# IoT_Remote_Control.net
KiCad netlist of a schematic drawn in EAGLE
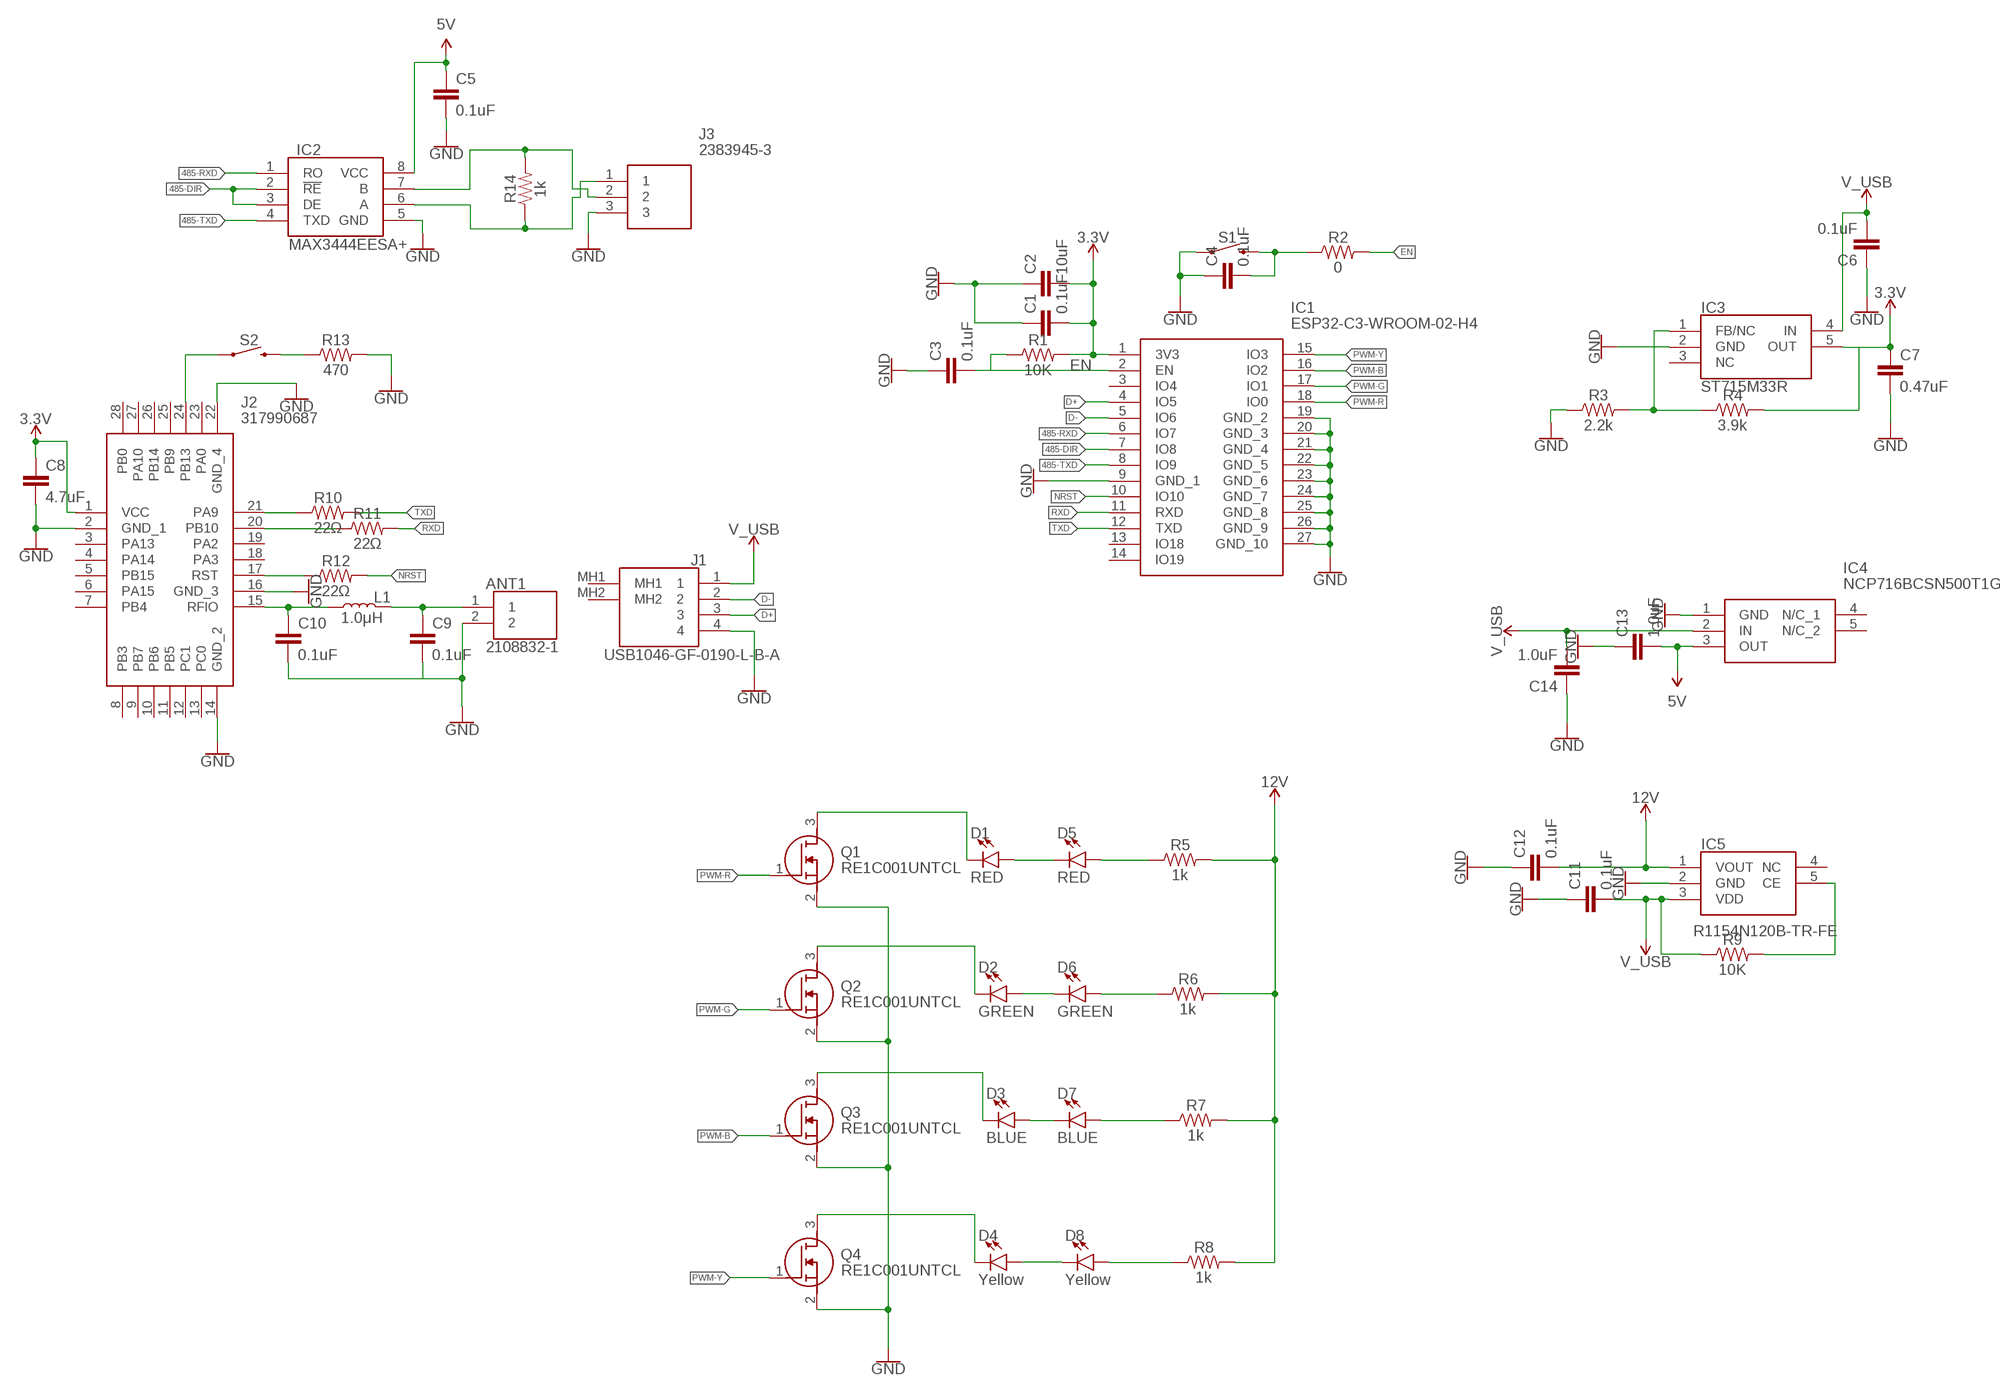
[diagram p0: schematic, sheet 1]

(export (version "E")
  (design (tool "Eeschema 10.0.6"))
  (components
    (comp (ref "ANT1")
      (value "2108832-1")
      (footprint "eagle-import:21088321")
      (libsource (lib "eagle-import") (part "2108832-1"))
    )
    (comp (ref "C1")
      (value "0.1uF")
      (footprint "eagle-import:0402-TIGHT")
      (libsource (lib "eagle-import") (part "0.1UF-0402T-6.3V-10%-X7R"))
    )
    (comp (ref "C2")
      (value "10uF")
      (footprint "eagle-import:0402-TIGHT")
      (libsource (lib "eagle-import") (part "10UF-0402T-6.3V-20%"))
    )
    (comp (ref "C3")
      (value "0.1uF")
      (footprint "eagle-import:0402-TIGHT")
      (libsource (lib "eagle-import") (part "0.1UF-0402T-6.3V-10%-X7R"))
    )
    (comp (ref "C4")
      (value "0.1uF")
      (footprint "eagle-import:0402-TIGHT")
      (libsource (lib "eagle-import") (part "0.1UF-0402T-6.3V-10%-X7R"))
    )
    (comp (ref "C5")
      (value "0.1uF")
      (footprint "eagle-import:0402-TIGHT")
      (libsource (lib "eagle-import") (part "0.1UF-0402T-6.3V-10%-X7R"))
    )
    (comp (ref "C6")
      (value "0.1uF")
      (footprint "eagle-import:0402-TIGHT")
      (libsource (lib "eagle-import") (part "0.1UF-0402T-6.3V-10%-X7R"))
    )
    (comp (ref "C7")
      (value "0.47uF")
      (footprint "eagle-import:0402-TIGHT")
      (libsource (lib "eagle-import") (part "470NF-0402_TIGHT-6.3V-10%-X5R"))
    )
    (comp (ref "C8")
      (value "4.7uF")
      (footprint "eagle-import:0402-TIGHT")
      (libsource (lib "eagle-import") (part "4.7UF-0402_TIGHT-6.3V-20%-X5R"))
    )
    (comp (ref "C9")
      (value "0.1uF")
      (footprint "eagle-import:0402-TIGHT")
      (libsource (lib "eagle-import") (part "0.1UF-0402T-6.3V-10%-X7R"))
    )
    (comp (ref "C10")
      (value "0.1uF")
      (footprint "eagle-import:0402-TIGHT")
      (libsource (lib "eagle-import") (part "0.1UF-0402T-6.3V-10%-X7R"))
    )
    (comp (ref "C11")
      (value "0.1uF")
      (footprint "eagle-import:0402-TIGHT")
      (libsource (lib "eagle-import") (part "0.1UF-0402T-6.3V-10%-X7R"))
    )
    (comp (ref "C12")
      (value "0.1uF")
      (footprint "eagle-import:0402-TIGHT")
      (libsource (lib "eagle-import") (part "0.1UF-0402T-6.3V-10%-X7R"))
    )
    (comp (ref "C13")
      (value "1.0uF")
      (footprint "eagle-import:0402-TIGHT")
      (libsource (lib "eagle-import") (part "1.0UF-0402T-16V-10%"))
    )
    (comp (ref "C14")
      (value "1.0uF")
      (footprint "eagle-import:0402-TIGHT")
      (libsource (lib "eagle-import") (part "1.0UF-0402T-16V-10%"))
    )
    (comp (ref "D1")
      (value "RED")
      (footprint "eagle-import:LED-0603")
      (libsource (lib "eagle-import") (part "LED-RED0603"))
    )
    (comp (ref "D2")
      (value "GREEN")
      (footprint "eagle-import:LED-0603")
      (libsource (lib "eagle-import") (part "LED-GREEN0603"))
    )
    (comp (ref "D3")
      (value "BLUE")
      (footprint "eagle-import:LED-0603")
      (libsource (lib "eagle-import") (part "LED-BLUE0603"))
    )
    (comp (ref "D4")
      (value "Yellow")
      (footprint "eagle-import:LED-0603")
      (libsource (lib "eagle-import") (part "LED-YELLOW0603"))
    )
    (comp (ref "D5")
      (value "RED")
      (footprint "eagle-import:LED-0603")
      (libsource (lib "eagle-import") (part "LED-RED0603"))
    )
    (comp (ref "D6")
      (value "GREEN")
      (footprint "eagle-import:LED-0603")
      (libsource (lib "eagle-import") (part "LED-GREEN0603"))
    )
    (comp (ref "D7")
      (value "BLUE")
      (footprint "eagle-import:LED-0603")
      (libsource (lib "eagle-import") (part "LED-BLUE0603"))
    )
    (comp (ref "D8")
      (value "Yellow")
      (footprint "eagle-import:LED-0603")
      (libsource (lib "eagle-import") (part "LED-YELLOW0603"))
    )
    (comp (ref "IC1")
      (value "ESP32-C3-WROOM-02-H4")
      (footprint "eagle-import:ESP32C3WROOM02H4")
      (fields (field (name "MOUSER_PART_NUMBER") "356-ESP32C3WROOM02H4"))
      (libsource (lib "eagle-import") (part "ESP32-C3-WROOM-02-H4"))
    )
    (comp (ref "IC2")
      (value "MAX3444EESA+")
      (footprint "eagle-import:SOIC127P600X175-8N")
      (fields (field (name "MOUSER_PART_NUMBER") "700-MAX3444EESA"))
      (libsource (lib "eagle-import") (part "MAX3444EESA+"))
    )
    (comp (ref "IC3")
      (value "ST715M33R")
      (footprint "eagle-import:SOT95P280X145-5N")
      (fields (field (name "MOUSER_PART_NUMBER") "511-ST715M33R"))
      (libsource (lib "eagle-import") (part "ST715M33R"))
    )
    (comp (ref "IC4")
      (value "NCP716BCSN500T1G")
      (footprint "eagle-import:SOT95P275X110-5N")
      (fields (field (name "MOUSER_PART_NUMBER") "863-NCP716BCSN500T1G"))
      (libsource (lib "eagle-import") (part "NCP716BCSN500T1G"))
    )
    (comp (ref "IC5")
      (value "R1154N120B-TR-FE")
      (footprint "eagle-import:SOT95P280X130-5N")
      (libsource (lib "eagle-import") (part "R1154N120B-TR-FE"))
    )
    (comp (ref "J1")
      (value "USB1046-GF-0190-L-B-A")
      (footprint "eagle-import:USB1046GF0190LBA")
      (fields (field (name "MOUSER_PART_NUMBER") "640-USB1046GF0190LBA"))
      (libsource (lib "eagle-import") (part "USB1046-GF-0190-L-B-A"))
    )
    (comp (ref "J2")
      (value "317990687")
      (footprint "eagle-import:317990687")
      (fields (field (name "MOUSER_PART_NUMBER") "713-317990687"))
      (libsource (lib "eagle-import") (part "317990687"))
    )
    (comp (ref "J3")
      (value "2383945-3")
      (footprint "eagle-import:23839453")
      (fields (field (name "MOUSER_PART_NUMBER") "571-2383945-3"))
      (libsource (lib "eagle-import") (part "2383945-3"))
    )
    (comp (ref "L1")
      (value "1.0μH")
      (footprint "eagle-import:0805-WIDE")
      (libsource (lib "eagle-import") (part "1.0μH-0805_WIDE-1.0μH-1.4A-0.07OHM-1.4MM_H"))
    )
    (comp (ref "Q1")
      (value "RE1C001UNTCL")
      (footprint "eagle-import:SOTFL50P160X85-3N")
      (fields (field (name "MOUSER_PART_NUMBER") "755-RE1C001UNTCL"))
      (libsource (lib "eagle-import") (part "RE1C001UNTCL"))
    )
    (comp (ref "Q2")
      (value "RE1C001UNTCL")
      (footprint "eagle-import:SOTFL50P160X85-3N")
      (fields (field (name "MOUSER_PART_NUMBER") "755-RE1C001UNTCL"))
      (libsource (lib "eagle-import") (part "RE1C001UNTCL"))
    )
    (comp (ref "Q3")
      (value "RE1C001UNTCL")
      (footprint "eagle-import:SOTFL50P160X85-3N")
      (fields (field (name "MOUSER_PART_NUMBER") "755-RE1C001UNTCL"))
      (libsource (lib "eagle-import") (part "RE1C001UNTCL"))
    )
    (comp (ref "Q4")
      (value "RE1C001UNTCL")
      (footprint "eagle-import:SOTFL50P160X85-3N")
      (fields (field (name "MOUSER_PART_NUMBER") "755-RE1C001UNTCL"))
      (libsource (lib "eagle-import") (part "RE1C001UNTCL"))
    )
    (comp (ref "R1")
      (value "10K")
      (footprint "eagle-import:0402-TIGHT")
      (libsource (lib "eagle-import") (part "10KOHM-0402-1/10W-0.1%"))
    )
    (comp (ref "R2")
      (value "0")
      (footprint "eagle-import:0402-TIGHT")
      (libsource (lib "eagle-import") (part "0OHM-0402T-1/10W"))
    )
    (comp (ref "R3")
      (value "2.2k")
      (footprint "eagle-import:0402-TIGHT")
      (libsource (lib "eagle-import") (part "2.2KOHM-0402T-1/16W-1%"))
    )
    (comp (ref "R4")
      (value "3.9k")
      (footprint "eagle-import:0603")
      (libsource (lib "eagle-import") (part "3.9KOHM-0603-1/10W-1%"))
    )
    (comp (ref "R5")
      (value "1k")
      (footprint "eagle-import:0402-TIGHT")
      (libsource (lib "eagle-import") (part "1KOHM-0402T-1/16W-1%"))
    )
    (comp (ref "R6")
      (value "1k")
      (footprint "eagle-import:0402-TIGHT")
      (libsource (lib "eagle-import") (part "1KOHM-0402T-1/16W-1%"))
    )
    (comp (ref "R7")
      (value "1k")
      (footprint "eagle-import:0402-TIGHT")
      (libsource (lib "eagle-import") (part "1KOHM-0402T-1/16W-1%"))
    )
    (comp (ref "R8")
      (value "1k")
      (footprint "eagle-import:0402-TIGHT")
      (libsource (lib "eagle-import") (part "1KOHM-0402T-1/16W-1%"))
    )
    (comp (ref "R9")
      (value "10K")
      (footprint "eagle-import:0402-TIGHT")
      (libsource (lib "eagle-import") (part "10KOHM-0402-1/10W-0.1%"))
    )
    (comp (ref "R10")
      (value "22Ω")
      (footprint "eagle-import:0402-TIGHT")
      (libsource (lib "eagle-import") (part "22OHM-0402T-1/16W-1%"))
    )
    (comp (ref "R11")
      (value "22Ω")
      (footprint "eagle-import:0402-TIGHT")
      (libsource (lib "eagle-import") (part "22OHM-0402T-1/16W-1%"))
    )
    (comp (ref "R12")
      (value "22Ω")
      (footprint "eagle-import:0402-TIGHT")
      (libsource (lib "eagle-import") (part "22OHM-0402T-1/16W-1%"))
    )
    (comp (ref "R13")
      (value "470")
      (footprint "eagle-import:0402-TIGHT")
      (libsource (lib "eagle-import") (part "470OHM-0402-TIGHT-1/16W-1%"))
    )
    (comp (ref "R14")
      (value "1k")
      (footprint "eagle-import:0402-TIGHT")
      (libsource (lib "eagle-import") (part "1KOHM-0402T-1/16W-1%"))
    )
    (comp (ref "S1")
      (value "MOMENTARY-SWITCH-SPST-SMD-4.6X2.8MM")
      (footprint "eagle-import:TACTILE_SWITCH_SMD_4.6X2.8MM")
      (libsource (lib "eagle-import") (part "MOMENTARY-SWITCH-SPST-SMD-4.6X2.8MM"))
    )
    (comp (ref "S2")
      (value "MOMENTARY-SWITCH-SPST-SMD-4.6X2.8MM")
      (footprint "eagle-import:TACTILE_SWITCH_SMD_4.6X2.8MM")
      (libsource (lib "eagle-import") (part "MOMENTARY-SWITCH-SPST-SMD-4.6X2.8MM"))
    )
  )
  (nets
    (net (code "1") (name "3.3V") (class "Default")
      (node (ref "C1") (pin "2") (pinfunction "2_2") (pintype "passive"))
      (node (ref "C2") (pin "2") (pinfunction "2_2") (pintype "passive"))
      (node (ref "C7") (pin "1") (pinfunction "1_1") (pintype "passive"))
      (node (ref "C8") (pin "1") (pinfunction "1_1") (pintype "passive"))
      (node (ref "IC1") (pin "1") (pinfunction "3V3_1") (pintype "bidirectional"))
      (node (ref "IC3") (pin "5") (pinfunction "OUT_5") (pintype "output"))
      (node (ref "J2") (pin "1") (pinfunction "VCC_1") (pintype "bidirectional"))
      (node (ref "R1") (pin "2") (pinfunction "2_2") (pintype "passive"))
      (node (ref "R4") (pin "2") (pinfunction "2_2") (pintype "passive"))
    )
    (net (code "2") (name "5V") (class "Default")
      (node (ref "C13") (pin "2") (pinfunction "2_2") (pintype "passive"))
      (node (ref "C5") (pin "1") (pinfunction "1_1") (pintype "passive"))
      (node (ref "IC2") (pin "8") (pinfunction "VCC_8") (pintype "bidirectional"))
      (node (ref "IC4") (pin "3") (pinfunction "OUT_3") (pintype "bidirectional"))
    )
    (net (code "3") (name "12V") (class "Default")
      (node (ref "C12") (pin "2") (pinfunction "2_2") (pintype "passive"))
      (node (ref "IC5") (pin "1") (pinfunction "VOUT_1") (pintype "bidirectional"))
      (node (ref "R5") (pin "2") (pinfunction "2_2") (pintype "passive"))
      (node (ref "R6") (pin "2") (pinfunction "2_2") (pintype "passive"))
      (node (ref "R7") (pin "2") (pinfunction "2_2") (pintype "passive"))
      (node (ref "R8") (pin "2") (pinfunction "2_2") (pintype "passive"))
    )
    (net (code "4") (name "485-DIR") (class "Default")
      (node (ref "IC1") (pin "7") (pinfunction "IO8_7") (pintype "bidirectional"))
      (node (ref "IC2") (pin "2") (pinfunction "~{RE}_2") (pintype "bidirectional"))
      (node (ref "IC2") (pin "3") (pinfunction "DE_3") (pintype "bidirectional"))
    )
    (net (code "5") (name "485-RXD") (class "Default")
      (node (ref "IC1") (pin "6") (pinfunction "IO7_6") (pintype "bidirectional"))
      (node (ref "IC2") (pin "1") (pinfunction "RO_1") (pintype "bidirectional"))
    )
    (net (code "6") (name "485-TXD") (class "Default")
      (node (ref "IC1") (pin "8") (pinfunction "IO9_8") (pintype "bidirectional"))
      (node (ref "IC2") (pin "4") (pinfunction "TXD_4") (pintype "bidirectional"))
    )
    (net (code "7") (name "D+") (class "Default")
      (node (ref "IC1") (pin "4") (pinfunction "IO5_4") (pintype "bidirectional"))
      (node (ref "J1") (pin "3") (pinfunction "3_3") (pintype "bidirectional"))
    )
    (net (code "8") (name "D-") (class "Default")
      (node (ref "IC1") (pin "5") (pinfunction "IO6_5") (pintype "bidirectional"))
      (node (ref "J1") (pin "2") (pinfunction "2_2") (pintype "bidirectional"))
    )
    (net (code "9") (name "EN") (class "Default")
      (node (ref "C3") (pin "2") (pinfunction "2_2") (pintype "passive"))
      (node (ref "IC1") (pin "2") (pinfunction "EN_2") (pintype "bidirectional"))
      (node (ref "R2") (pin "2") (pinfunction "2_2") (pintype "passive"))
    )
    (net (code "10") (name "GND") (class "Default")
      (node (ref "ANT1") (pin "2") (pinfunction "2_2") (pintype "bidirectional"))
      (node (ref "C1") (pin "1") (pinfunction "1_1") (pintype "passive"))
      (node (ref "C10") (pin "2") (pinfunction "2_2") (pintype "passive"))
      (node (ref "C11") (pin "1") (pinfunction "1_1") (pintype "passive"))
      (node (ref "C12") (pin "1") (pinfunction "1_1") (pintype "passive"))
      (node (ref "C13") (pin "1") (pinfunction "1_1") (pintype "passive"))
      (node (ref "C14") (pin "1") (pinfunction "1_1") (pintype "passive"))
      (node (ref "C2") (pin "1") (pinfunction "1_1") (pintype "passive"))
      (node (ref "C3") (pin "1") (pinfunction "1_1") (pintype "passive"))
      (node (ref "C4") (pin "1") (pinfunction "1_1") (pintype "passive"))
      (node (ref "C5") (pin "2") (pinfunction "2_2") (pintype "passive"))
      (node (ref "C6") (pin "1") (pinfunction "1_1") (pintype "passive"))
      (node (ref "C7") (pin "2") (pinfunction "2_2") (pintype "passive"))
      (node (ref "C8") (pin "2") (pinfunction "2_2") (pintype "passive"))
      (node (ref "IC1") (pin "19") (pinfunction "GND_2_19") (pintype "bidirectional"))
      (node (ref "IC1") (pin "20") (pinfunction "GND_3_20") (pintype "bidirectional"))
      (node (ref "IC1") (pin "21") (pinfunction "GND_4_21") (pintype "bidirectional"))
      (node (ref "IC1") (pin "22") (pinfunction "GND_5_22") (pintype "bidirectional"))
      (node (ref "IC1") (pin "23") (pinfunction "GND_6_23") (pintype "bidirectional"))
      (node (ref "IC1") (pin "24") (pinfunction "GND_7_24") (pintype "bidirectional"))
      (node (ref "IC1") (pin "25") (pinfunction "GND_8_25") (pintype "bidirectional"))
      (node (ref "IC1") (pin "26") (pinfunction "GND_9_26") (pintype "bidirectional"))
      (node (ref "IC1") (pin "27") (pinfunction "GND_10_27") (pintype "bidirectional"))
      (node (ref "IC1") (pin "9") (pinfunction "GND_1_9") (pintype "bidirectional"))
      (node (ref "IC2") (pin "5") (pinfunction "GND_5") (pintype "bidirectional"))
      (node (ref "IC3") (pin "2") (pinfunction "GND_2") (pintype "power_in"))
      (node (ref "IC4") (pin "1") (pinfunction "GND_1") (pintype "bidirectional"))
      (node (ref "IC5") (pin "2") (pinfunction "GND_2") (pintype "bidirectional"))
      (node (ref "J1") (pin "4") (pinfunction "4_4") (pintype "bidirectional"))
      (node (ref "J2") (pin "14") (pinfunction "GND_2_14") (pintype "bidirectional"))
      (node (ref "J2") (pin "16") (pinfunction "GND_3_16") (pintype "bidirectional"))
      (node (ref "J2") (pin "2") (pinfunction "GND_1_2") (pintype "bidirectional"))
      (node (ref "J2") (pin "22") (pinfunction "GND_4_22") (pintype "bidirectional"))
      (node (ref "J3") (pin "3") (pinfunction "3_3") (pintype "bidirectional"))
      (node (ref "Q1") (pin "2") (pinfunction "S_2") (pintype "bidirectional"))
      (node (ref "Q2") (pin "2") (pinfunction "S_2") (pintype "bidirectional"))
      (node (ref "Q3") (pin "2") (pinfunction "S_2") (pintype "bidirectional"))
      (node (ref "Q4") (pin "2") (pinfunction "S_2") (pintype "bidirectional"))
      (node (ref "R13") (pin "2") (pinfunction "2_2") (pintype "passive"))
      (node (ref "R3") (pin "1") (pinfunction "1_1") (pintype "passive"))
      (node (ref "S1") (pin "1") (pinfunction "1_1") (pintype "passive"))
      (node (ref "S1") (pin "2") (pinfunction "1_2") (pintype "passive"))
    )
    (net (code "11") (name "NRST") (class "Default")
      (node (ref "IC1") (pin "10") (pinfunction "IO10_10") (pintype "bidirectional"))
      (node (ref "R12") (pin "2") (pinfunction "2_2") (pintype "passive"))
    )
    (net (code "12") (name "Net-(ANT1-Pad1)") (class "Default")
      (node (ref "ANT1") (pin "1") (pinfunction "1_1") (pintype "bidirectional"))
      (node (ref "C9") (pin "1") (pinfunction "1_1") (pintype "passive"))
      (node (ref "L1") (pin "2") (pinfunction "2_2") (pintype "passive"))
    )
    (net (code "13") (name "Net-(C4-Pad2)") (class "Default")
      (node (ref "C4") (pin "2") (pinfunction "2_2") (pintype "passive"))
      (node (ref "R2") (pin "1") (pinfunction "1_1") (pintype "passive"))
      (node (ref "S1") (pin "3") (pinfunction "2_3") (pintype "passive"))
      (node (ref "S1") (pin "4") (pinfunction "2_4") (pintype "passive"))
    )
    (net (code "14") (name "Net-(D1-PadA)") (class "Default")
      (node (ref "D1") (pin "A") (pinfunction "A_A") (pintype "passive"))
      (node (ref "D5") (pin "C") (pinfunction "C_C") (pintype "passive"))
    )
    (net (code "15") (name "Net-(D2-PadA)") (class "Default")
      (node (ref "D2") (pin "A") (pinfunction "A_A") (pintype "passive"))
      (node (ref "D6") (pin "C") (pinfunction "C_C") (pintype "passive"))
    )
    (net (code "16") (name "Net-(D3-PadA)") (class "Default")
      (node (ref "D3") (pin "A") (pinfunction "A_A") (pintype "passive"))
      (node (ref "D7") (pin "C") (pinfunction "C_C") (pintype "passive"))
    )
    (net (code "17") (name "Net-(D4-PadA)") (class "Default")
      (node (ref "D4") (pin "A") (pinfunction "A_A") (pintype "passive"))
      (node (ref "D8") (pin "C") (pinfunction "C_C") (pintype "passive"))
    )
    (net (code "18") (name "Net-(D5-PadA)") (class "Default")
      (node (ref "D5") (pin "A") (pinfunction "A_A") (pintype "passive"))
      (node (ref "R5") (pin "1") (pinfunction "1_1") (pintype "passive"))
    )
    (net (code "19") (name "Net-(D6-PadA)") (class "Default")
      (node (ref "D6") (pin "A") (pinfunction "A_A") (pintype "passive"))
      (node (ref "R6") (pin "1") (pinfunction "1_1") (pintype "passive"))
    )
    (net (code "20") (name "Net-(D7-PadA)") (class "Default")
      (node (ref "D7") (pin "A") (pinfunction "A_A") (pintype "passive"))
      (node (ref "R7") (pin "1") (pinfunction "1_1") (pintype "passive"))
    )
    (net (code "21") (name "Net-(D8-PadA)") (class "Default")
      (node (ref "D8") (pin "A") (pinfunction "A_A") (pintype "passive"))
      (node (ref "R8") (pin "1") (pinfunction "1_1") (pintype "passive"))
    )
    (net (code "22") (name "Net-(IC2-A)") (class "Default")
      (node (ref "IC2") (pin "6") (pinfunction "A_6") (pintype "bidirectional"))
      (node (ref "J3") (pin "1") (pinfunction "1_1") (pintype "bidirectional"))
      (node (ref "R14") (pin "1") (pinfunction "1_1") (pintype "passive"))
    )
    (net (code "23") (name "Net-(IC2-B)") (class "Default")
      (node (ref "IC2") (pin "7") (pinfunction "B_7") (pintype "bidirectional"))
      (node (ref "J3") (pin "2") (pinfunction "2_2") (pintype "bidirectional"))
      (node (ref "R14") (pin "2") (pinfunction "2_2") (pintype "passive"))
    )
    (net (code "24") (name "Net-(IC3-FB{slash}NC)") (class "Default")
      (node (ref "IC3") (pin "1") (pinfunction "FB/NC_1") (pintype "bidirectional"))
      (node (ref "R3") (pin "2") (pinfunction "2_2") (pintype "passive"))
      (node (ref "R4") (pin "1") (pinfunction "1_1") (pintype "passive"))
    )
    (net (code "25") (name "Net-(IC5-CE)") (class "Default")
      (node (ref "IC5") (pin "5") (pinfunction "CE_5") (pintype "bidirectional"))
      (node (ref "R9") (pin "2") (pinfunction "2_2") (pintype "passive"))
    )
    (net (code "26") (name "Net-(J2-PA9)") (class "Default")
      (node (ref "J2") (pin "21") (pinfunction "PA9_21") (pintype "bidirectional"))
      (node (ref "R10") (pin "1") (pinfunction "1_1") (pintype "passive"))
    )
    (net (code "27") (name "Net-(J2-PB10)") (class "Default")
      (node (ref "J2") (pin "20") (pinfunction "PB10_20") (pintype "bidirectional"))
      (node (ref "R11") (pin "1") (pinfunction "1_1") (pintype "passive"))
    )
    (net (code "28") (name "Net-(J2-PB13)") (class "Default")
      (node (ref "J2") (pin "24") (pinfunction "PB13_24") (pintype "bidirectional"))
      (node (ref "S2") (pin "1") (pinfunction "1_1") (pintype "passive"))
      (node (ref "S2") (pin "2") (pinfunction "1_2") (pintype "passive"))
    )
    (net (code "29") (name "Net-(J2-RFIO)") (class "Default")
      (node (ref "C10") (pin "1") (pinfunction "1_1") (pintype "passive"))
      (node (ref "J2") (pin "15") (pinfunction "RFIO_15") (pintype "bidirectional"))
      (node (ref "L1") (pin "1") (pinfunction "1_1") (pintype "passive"))
    )
    (net (code "30") (name "Net-(J2-RST)") (class "Default")
      (node (ref "J2") (pin "17") (pinfunction "RST_17") (pintype "bidirectional"))
      (node (ref "R12") (pin "1") (pinfunction "1_1") (pintype "passive"))
    )
    (net (code "31") (name "Net-(Q1-D)") (class "Default")
      (node (ref "D1") (pin "C") (pinfunction "C_C") (pintype "passive"))
      (node (ref "Q1") (pin "3") (pinfunction "D_3") (pintype "bidirectional"))
    )
    (net (code "32") (name "Net-(Q2-D)") (class "Default")
      (node (ref "D2") (pin "C") (pinfunction "C_C") (pintype "passive"))
      (node (ref "Q2") (pin "3") (pinfunction "D_3") (pintype "bidirectional"))
    )
    (net (code "33") (name "Net-(Q3-D)") (class "Default")
      (node (ref "D3") (pin "C") (pinfunction "C_C") (pintype "passive"))
      (node (ref "Q3") (pin "3") (pinfunction "D_3") (pintype "bidirectional"))
    )
    (net (code "34") (name "Net-(Q4-D)") (class "Default")
      (node (ref "D4") (pin "C") (pinfunction "C_C") (pintype "passive"))
      (node (ref "Q4") (pin "3") (pinfunction "D_3") (pintype "bidirectional"))
    )
    (net (code "35") (name "Net-(R13-Pad1)") (class "Default")
      (node (ref "R13") (pin "1") (pinfunction "1_1") (pintype "passive"))
      (node (ref "S2") (pin "3") (pinfunction "2_3") (pintype "passive"))
      (node (ref "S2") (pin "4") (pinfunction "2_4") (pintype "passive"))
    )
    (net (code "36") (name "PWM-B") (class "Default")
      (node (ref "IC1") (pin "16") (pinfunction "IO2_16") (pintype "bidirectional"))
      (node (ref "Q3") (pin "1") (pinfunction "G_1") (pintype "bidirectional"))
    )
    (net (code "37") (name "PWM-G") (class "Default")
      (node (ref "IC1") (pin "17") (pinfunction "IO1_17") (pintype "bidirectional"))
      (node (ref "Q2") (pin "1") (pinfunction "G_1") (pintype "bidirectional"))
    )
    (net (code "38") (name "PWM-R") (class "Default")
      (node (ref "IC1") (pin "18") (pinfunction "IO0_18") (pintype "bidirectional"))
      (node (ref "Q1") (pin "1") (pinfunction "G_1") (pintype "bidirectional"))
    )
    (net (code "39") (name "PWM-Y") (class "Default")
      (node (ref "IC1") (pin "15") (pinfunction "IO3_15") (pintype "bidirectional"))
      (node (ref "Q4") (pin "1") (pinfunction "G_1") (pintype "bidirectional"))
    )
    (net (code "40") (name "RXD") (class "Default")
      (node (ref "IC1") (pin "11") (pinfunction "RXD_11") (pintype "bidirectional"))
      (node (ref "R11") (pin "2") (pinfunction "2_2") (pintype "passive"))
    )
    (net (code "41") (name "TXD") (class "Default")
      (node (ref "IC1") (pin "12") (pinfunction "TXD_12") (pintype "bidirectional"))
      (node (ref "R10") (pin "2") (pinfunction "2_2") (pintype "passive"))
    )
    (net (code "42") (name "V_USB") (class "Default")
      (node (ref "C11") (pin "2") (pinfunction "2_2") (pintype "passive"))
      (node (ref "C14") (pin "2") (pinfunction "2_2") (pintype "passive"))
      (node (ref "C6") (pin "2") (pinfunction "2_2") (pintype "passive"))
      (node (ref "IC3") (pin "4") (pinfunction "IN_4") (pintype "input"))
      (node (ref "IC4") (pin "2") (pinfunction "IN_2") (pintype "bidirectional"))
      (node (ref "IC5") (pin "3") (pinfunction "VDD_3") (pintype "bidirectional"))
      (node (ref "J1") (pin "1") (pinfunction "1_1") (pintype "bidirectional"))
      (node (ref "R9") (pin "1") (pinfunction "1_1") (pintype "passive"))
    )
    (net (code "43") (name "unconnected-(C9-Pad2)") (class "Default")
      (node (ref "C9") (pin "2") (pinfunction "2_2") (pintype "passive"))
    )
    (net (code "44") (name "unconnected-(IC1-IO4-Pad3)") (class "Default")
      (node (ref "IC1") (pin "3") (pinfunction "IO4_3") (pintype "bidirectional"))
    )
    (net (code "45") (name "unconnected-(IC1-IO18-Pad13)") (class "Default")
      (node (ref "IC1") (pin "13") (pinfunction "IO18_13") (pintype "bidirectional"))
    )
    (net (code "46") (name "unconnected-(IC1-IO19-Pad14)") (class "Default")
      (node (ref "IC1") (pin "14") (pinfunction "IO19_14") (pintype "bidirectional"))
    )
    (net (code "47") (name "unconnected-(IC3-NC-Pad3)") (class "Default")
      (node (ref "IC3") (pin "3") (pinfunction "NC_3") (pintype "no_connect"))
    )
    (net (code "48") (name "unconnected-(IC4-N{slash}C_1-Pad4)") (class "Default")
      (node (ref "IC4") (pin "4") (pinfunction "N/C_1_4") (pintype "bidirectional"))
    )
    (net (code "49") (name "unconnected-(IC4-N{slash}C_2-Pad5)") (class "Default")
      (node (ref "IC4") (pin "5") (pinfunction "N/C_2_5") (pintype "bidirectional"))
    )
    (net (code "50") (name "unconnected-(IC5-NC-Pad4)") (class "Default")
      (node (ref "IC5") (pin "4") (pinfunction "NC_4") (pintype "no_connect"))
    )
    (net (code "51") (name "unconnected-(J1-PadMH1)") (class "Default")
      (node (ref "J1") (pin "MH1") (pinfunction "MH1_MH1") (pintype "bidirectional"))
    )
    (net (code "52") (name "unconnected-(J1-PadMH2)") (class "Default")
      (node (ref "J1") (pin "MH2") (pinfunction "MH2_MH2") (pintype "bidirectional"))
    )
    (net (code "53") (name "unconnected-(J2-PA0-Pad23)") (class "Default")
      (node (ref "J2") (pin "23") (pinfunction "PA0_23") (pintype "bidirectional"))
    )
    (net (code "54") (name "unconnected-(J2-PA2-Pad19)") (class "Default")
      (node (ref "J2") (pin "19") (pinfunction "PA2_19") (pintype "bidirectional"))
    )
    (net (code "55") (name "unconnected-(J2-PA3-Pad18)") (class "Default")
      (node (ref "J2") (pin "18") (pinfunction "PA3_18") (pintype "bidirectional"))
    )
    (net (code "56") (name "unconnected-(J2-PA10-Pad27)") (class "Default")
      (node (ref "J2") (pin "27") (pinfunction "PA10_27") (pintype "bidirectional"))
    )
    (net (code "57") (name "unconnected-(J2-PA13-Pad3)") (class "Default")
      (node (ref "J2") (pin "3") (pinfunction "PA13_3") (pintype "bidirectional"))
    )
    (net (code "58") (name "unconnected-(J2-PA14-Pad4)") (class "Default")
      (node (ref "J2") (pin "4") (pinfunction "PA14_4") (pintype "bidirectional"))
    )
    (net (code "59") (name "unconnected-(J2-PA15-Pad6)") (class "Default")
      (node (ref "J2") (pin "6") (pinfunction "PA15_6") (pintype "bidirectional"))
    )
    (net (code "60") (name "unconnected-(J2-PB0-Pad28)") (class "Default")
      (node (ref "J2") (pin "28") (pinfunction "PB0_28") (pintype "bidirectional"))
    )
    (net (code "61") (name "unconnected-(J2-PB3-Pad8)") (class "Default")
      (node (ref "J2") (pin "8") (pinfunction "PB3_8") (pintype "bidirectional"))
    )
    (net (code "62") (name "unconnected-(J2-PB4-Pad7)") (class "Default")
      (node (ref "J2") (pin "7") (pinfunction "PB4_7") (pintype "bidirectional"))
    )
    (net (code "63") (name "unconnected-(J2-PB5-Pad11)") (class "Default")
      (node (ref "J2") (pin "11") (pinfunction "PB5_11") (pintype "bidirectional"))
    )
    (net (code "64") (name "unconnected-(J2-PB6-Pad10)") (class "Default")
      (node (ref "J2") (pin "10") (pinfunction "PB6_10") (pintype "bidirectional"))
    )
    (net (code "65") (name "unconnected-(J2-PB7-Pad9)") (class "Default")
      (node (ref "J2") (pin "9") (pinfunction "PB7_9") (pintype "bidirectional"))
    )
    (net (code "66") (name "unconnected-(J2-PB9-Pad25)") (class "Default")
      (node (ref "J2") (pin "25") (pinfunction "PB9_25") (pintype "bidirectional"))
    )
    (net (code "67") (name "unconnected-(J2-PB14-Pad26)") (class "Default")
      (node (ref "J2") (pin "26") (pinfunction "PB14_26") (pintype "bidirectional"))
    )
    (net (code "68") (name "unconnected-(J2-PB15-Pad5)") (class "Default")
      (node (ref "J2") (pin "5") (pinfunction "PB15_5") (pintype "bidirectional"))
    )
    (net (code "69") (name "unconnected-(J2-PC0-Pad13)") (class "Default")
      (node (ref "J2") (pin "13") (pinfunction "PC0_13") (pintype "bidirectional"))
    )
    (net (code "70") (name "unconnected-(J2-PC1-Pad12)") (class "Default")
      (node (ref "J2") (pin "12") (pinfunction "PC1_12") (pintype "bidirectional"))
    )
    (net (code "71") (name "unconnected-(R1-Pad1)") (class "Default")
      (node (ref "R1") (pin "1") (pinfunction "1_1") (pintype "passive"))
    )
  )
)
